# SwitchBreakout.net
KiCad netlist of a schematic drawn in Altium Designer
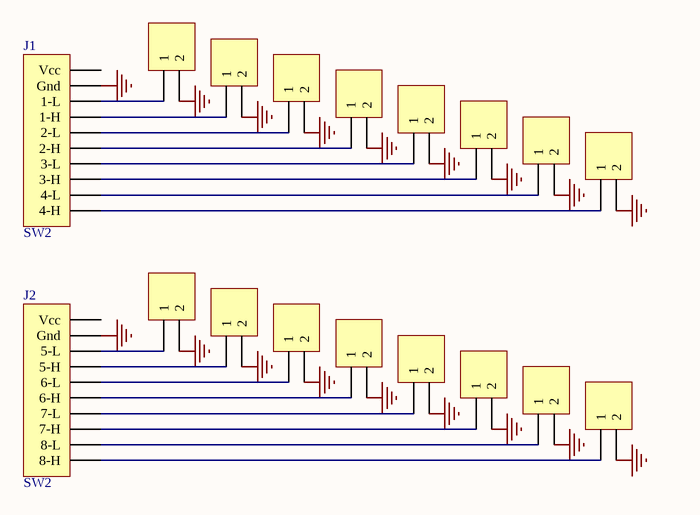
[diagram p0: SwitchBreakout.SchDoc]

(export (version "E")
  (design (tool "Eeschema 10.0.6"))
  (components
    (comp (ref "1-H")
      (value "1-H")
      (footprint "HDR1X2")
      (description "Header, 2-Pin")
      (fields (field (name "PUBLISHER") "Altium Limited"))
      (libsource (lib "Miscellaneous Connectors") (part "Header 2"))
    )
    (comp (ref "2-L")
      (value "2-L")
      (footprint "HDR1X2")
      (description "Header, 2-Pin")
      (fields (field (name "PUBLISHER") "Altium Limited"))
      (libsource (lib "Miscellaneous Connectors") (part "Header 2"))
    )
    (comp (ref "J1")
      (value "SW2")
      (footprint "0.1 SIP 10 PIN")
      (description "Header, 10-Pin")
      (fields (field (name "PUBLISHER") "Altium Limited"))
      (libsource (lib "Miscellaneous Connectors") (part "Header 10"))
    )
    (comp (ref "J2")
      (value "SW2")
      (footprint "0.1 SIP 10 PIN")
      (description "Header, 10-Pin")
      (fields (field (name "PUBLISHER") "Altium Limited"))
      (libsource (lib "Miscellaneous Connectors") (part "Header 10"))
    )
    (comp (ref "P1")
      (value "1-L")
      (footprint "HDR1X2")
      (description "Header, 2-Pin")
      (fields (field (name "PUBLISHER") "Altium Limited"))
      (libsource (lib "Miscellaneous Connectors") (part "Header 2"))
    )
    (comp (ref "P4")
      (value "2-H")
      (footprint "HDR1X2")
      (description "Header, 2-Pin")
      (fields (field (name "PUBLISHER") "Altium Limited"))
      (libsource (lib "Miscellaneous Connectors") (part "Header 2"))
    )
    (comp (ref "P5")
      (value "3-L")
      (footprint "HDR1X2")
      (description "Header, 2-Pin")
      (fields (field (name "PUBLISHER") "Altium Limited"))
      (libsource (lib "Miscellaneous Connectors") (part "Header 2"))
    )
    (comp (ref "P6")
      (value "3-H")
      (footprint "HDR1X2")
      (description "Header, 2-Pin")
      (fields (field (name "PUBLISHER") "Altium Limited"))
      (libsource (lib "Miscellaneous Connectors") (part "Header 2"))
    )
    (comp (ref "P7")
      (value "4-L")
      (footprint "HDR1X2")
      (description "Header, 2-Pin")
      (fields (field (name "PUBLISHER") "Altium Limited"))
      (libsource (lib "Miscellaneous Connectors") (part "Header 2"))
    )
    (comp (ref "P8")
      (value "4-H")
      (footprint "HDR1X2")
      (description "Header, 2-Pin")
      (fields (field (name "PUBLISHER") "Altium Limited"))
      (libsource (lib "Miscellaneous Connectors") (part "Header 2"))
    )
    (comp (ref "P9")
      (value "5-L")
      (footprint "HDR1X2")
      (description "Header, 2-Pin")
      (fields (field (name "PUBLISHER") "Altium Limited"))
      (libsource (lib "Miscellaneous Connectors") (part "Header 2"))
    )
    (comp (ref "P10")
      (value "5-H")
      (footprint "HDR1X2")
      (description "Header, 2-Pin")
      (fields (field (name "PUBLISHER") "Altium Limited"))
      (libsource (lib "Miscellaneous Connectors") (part "Header 2"))
    )
    (comp (ref "P11")
      (value "6-L")
      (footprint "HDR1X2")
      (description "Header, 2-Pin")
      (fields (field (name "PUBLISHER") "Altium Limited"))
      (libsource (lib "Miscellaneous Connectors") (part "Header 2"))
    )
    (comp (ref "P12")
      (value "6-H")
      (footprint "HDR1X2")
      (description "Header, 2-Pin")
      (fields (field (name "PUBLISHER") "Altium Limited"))
      (libsource (lib "Miscellaneous Connectors") (part "Header 2"))
    )
    (comp (ref "P13")
      (value "7-L")
      (footprint "HDR1X2")
      (description "Header, 2-Pin")
      (fields (field (name "PUBLISHER") "Altium Limited"))
      (libsource (lib "Miscellaneous Connectors") (part "Header 2"))
    )
    (comp (ref "P14")
      (value "7-H")
      (footprint "HDR1X2")
      (description "Header, 2-Pin")
      (fields (field (name "PUBLISHER") "Altium Limited"))
      (libsource (lib "Miscellaneous Connectors") (part "Header 2"))
    )
    (comp (ref "P15")
      (value "8-L")
      (footprint "HDR1X2")
      (description "Header, 2-Pin")
      (fields (field (name "PUBLISHER") "Altium Limited"))
      (libsource (lib "Miscellaneous Connectors") (part "Header 2"))
    )
    (comp (ref "P16")
      (value "8-H")
      (footprint "HDR1X2")
      (description "Header, 2-Pin")
      (fields (field (name "PUBLISHER") "Altium Limited"))
      (libsource (lib "Miscellaneous Connectors") (part "Header 2"))
    )
  )
  (nets
    (net (code "1") (name "GND") (class "Default")
      (node (ref "1-H") (pin "2") (pinfunction "2_2") (pintype "passive"))
      (node (ref "2-L") (pin "2") (pinfunction "2_2") (pintype "passive"))
      (node (ref "J1") (pin "2") (pinfunction "Gnd_2") (pintype "passive"))
      (node (ref "J2") (pin "2") (pinfunction "Gnd_2") (pintype "passive"))
      (node (ref "P1") (pin "2") (pinfunction "2_2") (pintype "passive"))
      (node (ref "P10") (pin "2") (pinfunction "2_2") (pintype "passive"))
      (node (ref "P11") (pin "2") (pinfunction "2_2") (pintype "passive"))
      (node (ref "P12") (pin "2") (pinfunction "2_2") (pintype "passive"))
      (node (ref "P13") (pin "2") (pinfunction "2_2") (pintype "passive"))
      (node (ref "P14") (pin "2") (pinfunction "2_2") (pintype "passive"))
      (node (ref "P15") (pin "2") (pinfunction "2_2") (pintype "passive"))
      (node (ref "P16") (pin "2") (pinfunction "2_2") (pintype "passive"))
      (node (ref "P4") (pin "2") (pinfunction "2_2") (pintype "passive"))
      (node (ref "P5") (pin "2") (pinfunction "2_2") (pintype "passive"))
      (node (ref "P6") (pin "2") (pinfunction "2_2") (pintype "passive"))
      (node (ref "P7") (pin "2") (pinfunction "2_2") (pintype "passive"))
      (node (ref "P8") (pin "2") (pinfunction "2_2") (pintype "passive"))
      (node (ref "P9") (pin "2") (pinfunction "2_2") (pintype "passive"))
    )
    (net (code "2") (name "Net-(J1-1-H)") (class "Default")
      (node (ref "1-H") (pin "1") (pinfunction "1_1") (pintype "passive"))
      (node (ref "J1") (pin "4") (pinfunction "1-H_4") (pintype "passive"))
    )
    (net (code "3") (name "Net-(J1-1-L)") (class "Default")
      (node (ref "J1") (pin "3") (pinfunction "1-L_3") (pintype "passive"))
      (node (ref "P1") (pin "1") (pinfunction "1_1") (pintype "passive"))
    )
    (net (code "4") (name "Net-(J1-2-H)") (class "Default")
      (node (ref "J1") (pin "6") (pinfunction "2-H_6") (pintype "passive"))
      (node (ref "P4") (pin "1") (pinfunction "1_1") (pintype "passive"))
    )
    (net (code "5") (name "Net-(J1-2-L)") (class "Default")
      (node (ref "2-L") (pin "1") (pinfunction "1_1") (pintype "passive"))
      (node (ref "J1") (pin "5") (pinfunction "2-L_5") (pintype "passive"))
    )
    (net (code "6") (name "Net-(J1-3-H)") (class "Default")
      (node (ref "J1") (pin "8") (pinfunction "3-H_8") (pintype "passive"))
      (node (ref "P6") (pin "1") (pinfunction "1_1") (pintype "passive"))
    )
    (net (code "7") (name "Net-(J1-3-L)") (class "Default")
      (node (ref "J1") (pin "7") (pinfunction "3-L_7") (pintype "passive"))
      (node (ref "P5") (pin "1") (pinfunction "1_1") (pintype "passive"))
    )
    (net (code "8") (name "Net-(J1-4-H)") (class "Default")
      (node (ref "J1") (pin "10") (pinfunction "4-H_10") (pintype "passive"))
      (node (ref "P8") (pin "1") (pinfunction "1_1") (pintype "passive"))
    )
    (net (code "9") (name "Net-(J1-4-L)") (class "Default")
      (node (ref "J1") (pin "9") (pinfunction "4-L_9") (pintype "passive"))
      (node (ref "P7") (pin "1") (pinfunction "1_1") (pintype "passive"))
    )
    (net (code "10") (name "Net-(J2-1-H)") (class "Default")
      (node (ref "J2") (pin "4") (pinfunction "1-H_4") (pintype "passive"))
      (node (ref "P10") (pin "1") (pinfunction "1_1") (pintype "passive"))
    )
    (net (code "11") (name "Net-(J2-1-L)") (class "Default")
      (node (ref "J2") (pin "3") (pinfunction "1-L_3") (pintype "passive"))
      (node (ref "P9") (pin "1") (pinfunction "1_1") (pintype "passive"))
    )
    (net (code "12") (name "Net-(J2-2-H)") (class "Default")
      (node (ref "J2") (pin "6") (pinfunction "2-H_6") (pintype "passive"))
      (node (ref "P12") (pin "1") (pinfunction "1_1") (pintype "passive"))
    )
    (net (code "13") (name "Net-(J2-2-L)") (class "Default")
      (node (ref "J2") (pin "5") (pinfunction "2-L_5") (pintype "passive"))
      (node (ref "P11") (pin "1") (pinfunction "1_1") (pintype "passive"))
    )
    (net (code "14") (name "Net-(J2-3-H)") (class "Default")
      (node (ref "J2") (pin "8") (pinfunction "3-H_8") (pintype "passive"))
      (node (ref "P14") (pin "1") (pinfunction "1_1") (pintype "passive"))
    )
    (net (code "15") (name "Net-(J2-3-L)") (class "Default")
      (node (ref "J2") (pin "7") (pinfunction "3-L_7") (pintype "passive"))
      (node (ref "P13") (pin "1") (pinfunction "1_1") (pintype "passive"))
    )
    (net (code "16") (name "Net-(J2-4-H)") (class "Default")
      (node (ref "J2") (pin "10") (pinfunction "4-H_10") (pintype "passive"))
      (node (ref "P16") (pin "1") (pinfunction "1_1") (pintype "passive"))
    )
    (net (code "17") (name "Net-(J2-4-L)") (class "Default")
      (node (ref "J2") (pin "9") (pinfunction "4-L_9") (pintype "passive"))
      (node (ref "P15") (pin "1") (pinfunction "1_1") (pintype "passive"))
    )
    (net (code "18") (name "unconnected-(J1-Vcc-Pad1)") (class "Default")
      (node (ref "J1") (pin "1") (pinfunction "Vcc_1") (pintype "passive"))
    )
    (net (code "19") (name "unconnected-(J2-Vcc-Pad1)") (class "Default")
      (node (ref "J2") (pin "1") (pinfunction "Vcc_1") (pintype "passive"))
    )
  )
)
